# Action_Buttons.net
KiCad netlist of a schematic drawn in EAGLE
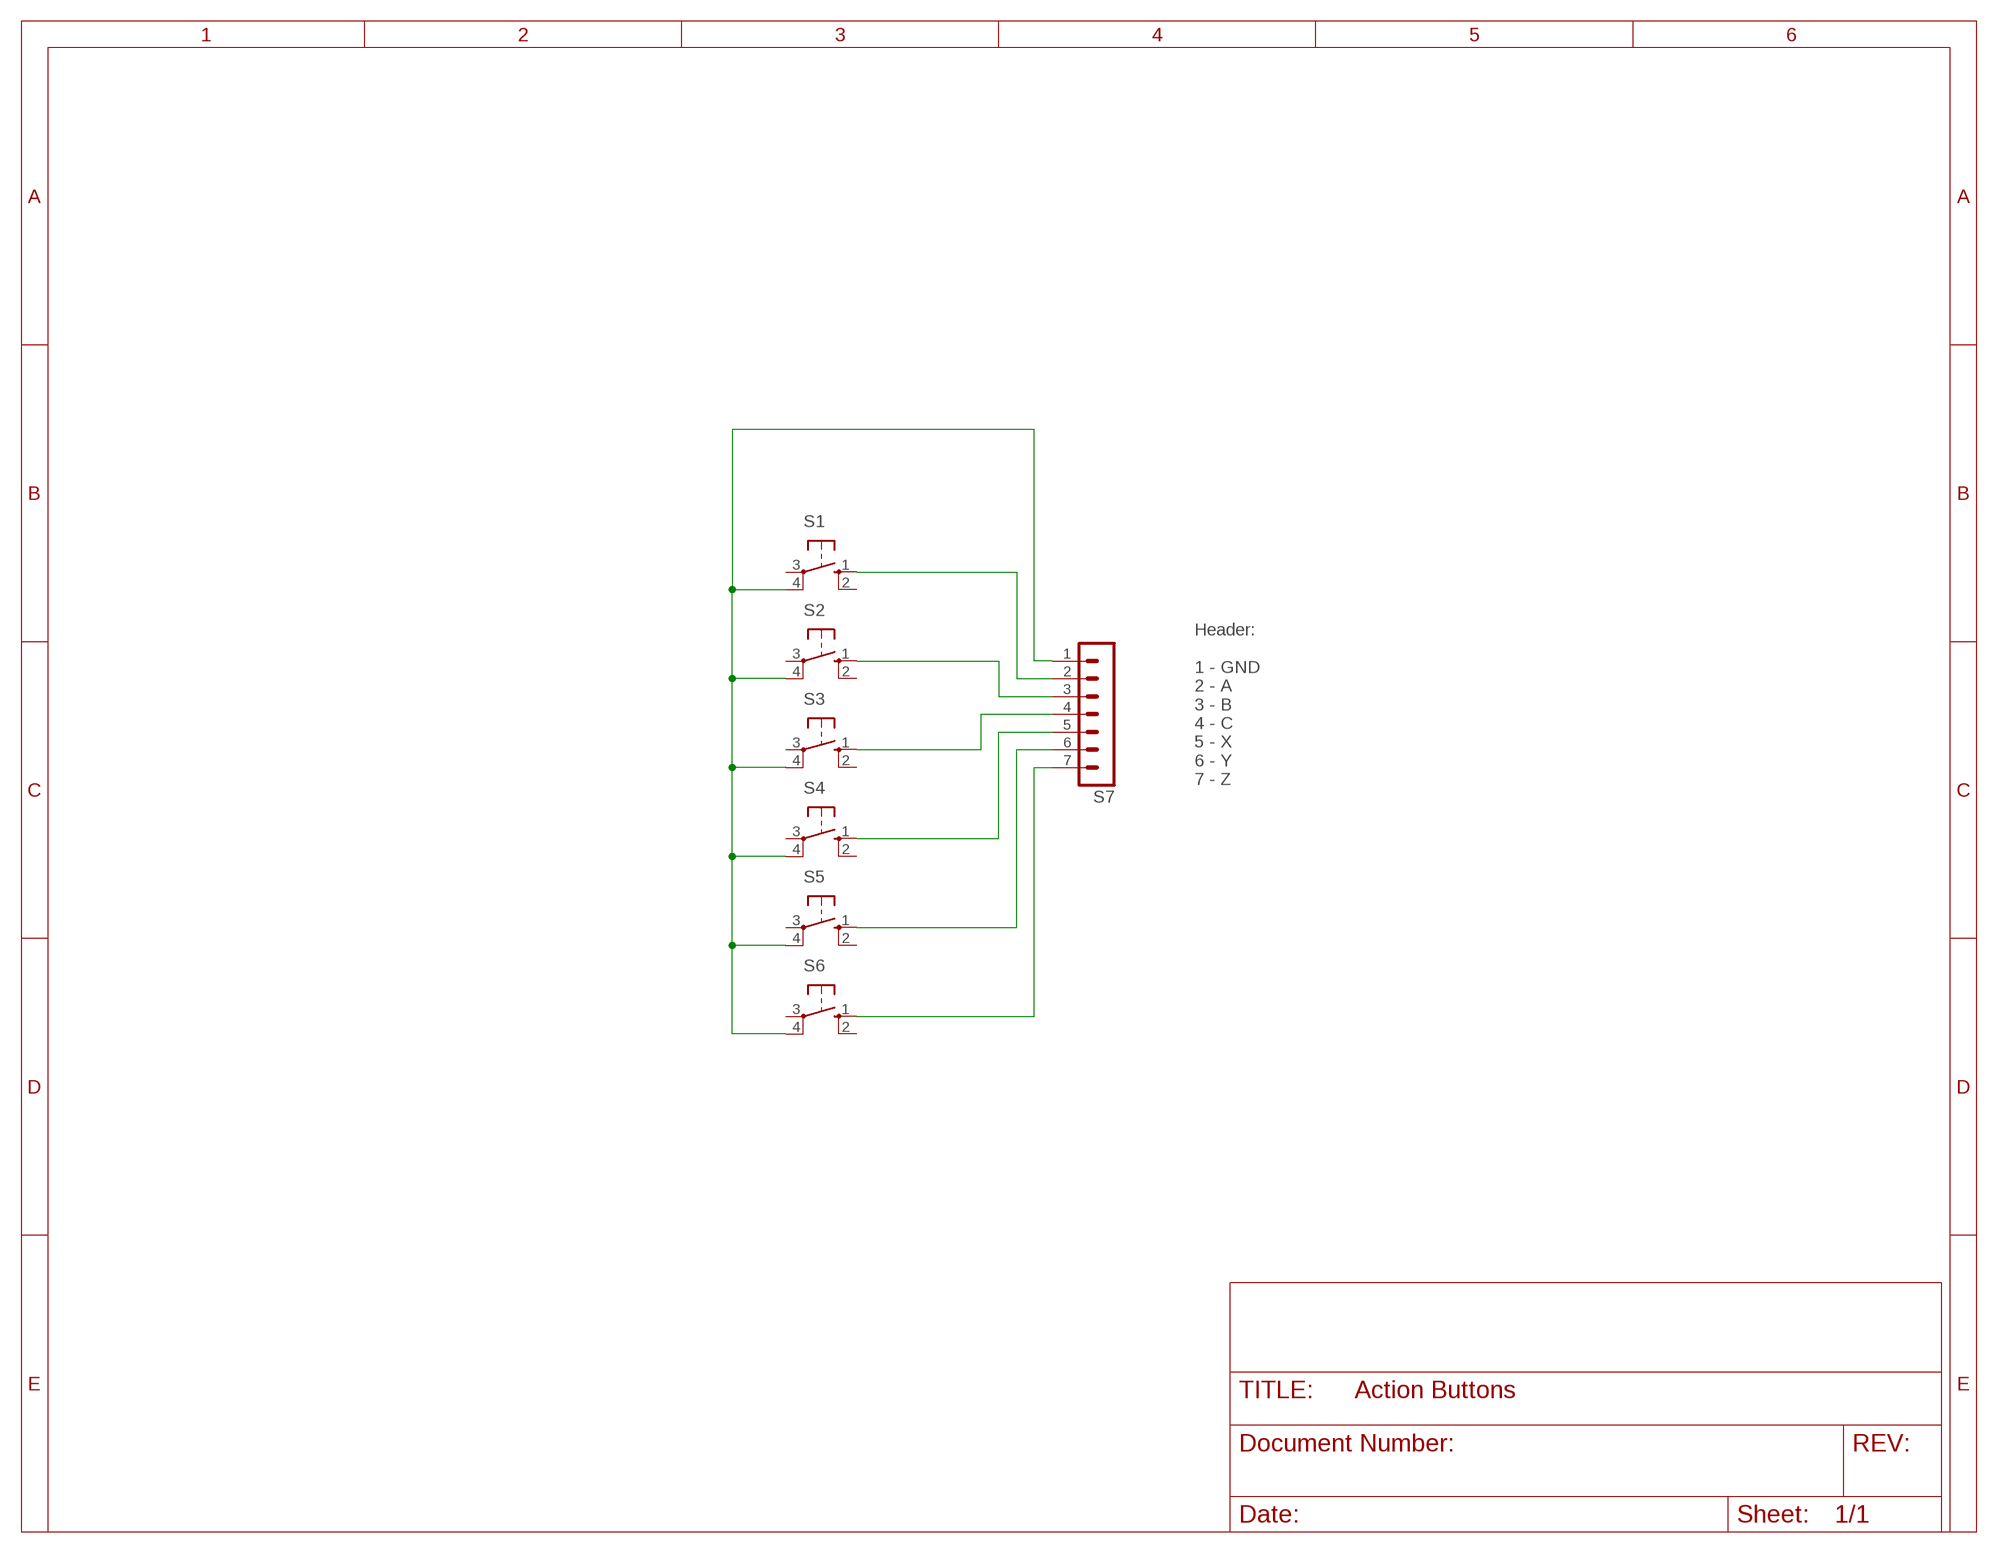
[diagram p0: schematic, sheet 1]

(export (version "E")
  (design (tool "Eeschema 10.0.6"))
  (components
    (comp (ref "S1")
      (value "10-XX")
      (footprint "eagle-import:B3F-10XX")
      (fields (field (name "MPN") "B3F-1000"))
      (libsource (lib "eagle-import") (part "10-XX"))
    )
    (comp (ref "S2")
      (value "10-XX")
      (footprint "eagle-import:B3F-10XX")
      (fields (field (name "MPN") "B3F-1000"))
      (libsource (lib "eagle-import") (part "10-XX"))
    )
    (comp (ref "S3")
      (value "10-XX")
      (footprint "eagle-import:B3F-10XX")
      (fields (field (name "MPN") "B3F-1000"))
      (libsource (lib "eagle-import") (part "10-XX"))
    )
    (comp (ref "S4")
      (value "10-XX")
      (footprint "eagle-import:B3F-10XX")
      (fields (field (name "MPN") "B3F-1000"))
      (libsource (lib "eagle-import") (part "10-XX"))
    )
    (comp (ref "S5")
      (value "10-XX")
      (footprint "eagle-import:B3F-10XX")
      (fields (field (name "MPN") "B3F-1000"))
      (libsource (lib "eagle-import") (part "10-XX"))
    )
    (comp (ref "S6")
      (value "10-XX")
      (footprint "eagle-import:B3F-10XX")
      (fields (field (name "MPN") "B3F-1000"))
      (libsource (lib "eagle-import") (part "10-XX"))
    )
    (comp (ref "S7")
      (value "MA07-1")
      (footprint "eagle-import:MA07-1")
      (libsource (lib "eagle-import") (part "MA07-1"))
    )
  )
  (nets
    (net (code "1") (name "Net-(S1-P1)") (class "Default")
      (node (ref "S1") (pin "4") (pinfunction "P1_4") (pintype "passive"))
      (node (ref "S2") (pin "4") (pinfunction "P1_4") (pintype "passive"))
      (node (ref "S3") (pin "4") (pinfunction "P1_4") (pintype "passive"))
      (node (ref "S4") (pin "4") (pinfunction "P1_4") (pintype "passive"))
      (node (ref "S5") (pin "4") (pinfunction "P1_4") (pintype "passive"))
      (node (ref "S6") (pin "4") (pinfunction "P1_4") (pintype "passive"))
      (node (ref "S7") (pin "1") (pinfunction "1_1") (pintype "passive"))
    )
    (net (code "2") (name "Net-(S1-S)") (class "Default")
      (node (ref "S1") (pin "1") (pinfunction "S_1") (pintype "passive"))
      (node (ref "S7") (pin "2") (pinfunction "2_2") (pintype "passive"))
    )
    (net (code "3") (name "Net-(S2-S)") (class "Default")
      (node (ref "S2") (pin "1") (pinfunction "S_1") (pintype "passive"))
      (node (ref "S7") (pin "3") (pinfunction "3_3") (pintype "passive"))
    )
    (net (code "4") (name "Net-(S3-S)") (class "Default")
      (node (ref "S3") (pin "1") (pinfunction "S_1") (pintype "passive"))
      (node (ref "S7") (pin "4") (pinfunction "4_4") (pintype "passive"))
    )
    (net (code "5") (name "Net-(S4-S)") (class "Default")
      (node (ref "S4") (pin "1") (pinfunction "S_1") (pintype "passive"))
      (node (ref "S7") (pin "5") (pinfunction "5_5") (pintype "passive"))
    )
    (net (code "6") (name "Net-(S5-S)") (class "Default")
      (node (ref "S5") (pin "1") (pinfunction "S_1") (pintype "passive"))
      (node (ref "S7") (pin "6") (pinfunction "6_6") (pintype "passive"))
    )
    (net (code "7") (name "Net-(S6-S)") (class "Default")
      (node (ref "S6") (pin "1") (pinfunction "S_1") (pintype "passive"))
      (node (ref "S7") (pin "7") (pinfunction "7_7") (pintype "passive"))
    )
    (net (code "8") (name "unconnected-(S1-P-Pad3)") (class "Default")
      (node (ref "S1") (pin "3") (pinfunction "P_3") (pintype "passive"))
    )
    (net (code "9") (name "unconnected-(S1-S1-Pad2)") (class "Default")
      (node (ref "S1") (pin "2") (pinfunction "S1_2") (pintype "passive"))
    )
    (net (code "10") (name "unconnected-(S2-P-Pad3)") (class "Default")
      (node (ref "S2") (pin "3") (pinfunction "P_3") (pintype "passive"))
    )
    (net (code "11") (name "unconnected-(S2-S1-Pad2)") (class "Default")
      (node (ref "S2") (pin "2") (pinfunction "S1_2") (pintype "passive"))
    )
    (net (code "12") (name "unconnected-(S3-P-Pad3)") (class "Default")
      (node (ref "S3") (pin "3") (pinfunction "P_3") (pintype "passive"))
    )
    (net (code "13") (name "unconnected-(S3-S1-Pad2)") (class "Default")
      (node (ref "S3") (pin "2") (pinfunction "S1_2") (pintype "passive"))
    )
    (net (code "14") (name "unconnected-(S4-P-Pad3)") (class "Default")
      (node (ref "S4") (pin "3") (pinfunction "P_3") (pintype "passive"))
    )
    (net (code "15") (name "unconnected-(S4-S1-Pad2)") (class "Default")
      (node (ref "S4") (pin "2") (pinfunction "S1_2") (pintype "passive"))
    )
    (net (code "16") (name "unconnected-(S5-P-Pad3)") (class "Default")
      (node (ref "S5") (pin "3") (pinfunction "P_3") (pintype "passive"))
    )
    (net (code "17") (name "unconnected-(S5-S1-Pad2)") (class "Default")
      (node (ref "S5") (pin "2") (pinfunction "S1_2") (pintype "passive"))
    )
    (net (code "18") (name "unconnected-(S6-P-Pad3)") (class "Default")
      (node (ref "S6") (pin "3") (pinfunction "P_3") (pintype "passive"))
    )
    (net (code "19") (name "unconnected-(S6-S1-Pad2)") (class "Default")
      (node (ref "S6") (pin "2") (pinfunction "S1_2") (pintype "passive"))
    )
  )
)
